# Terminal_Board_Schematic.net
KiCad netlist of a schematic drawn in Altium Designer
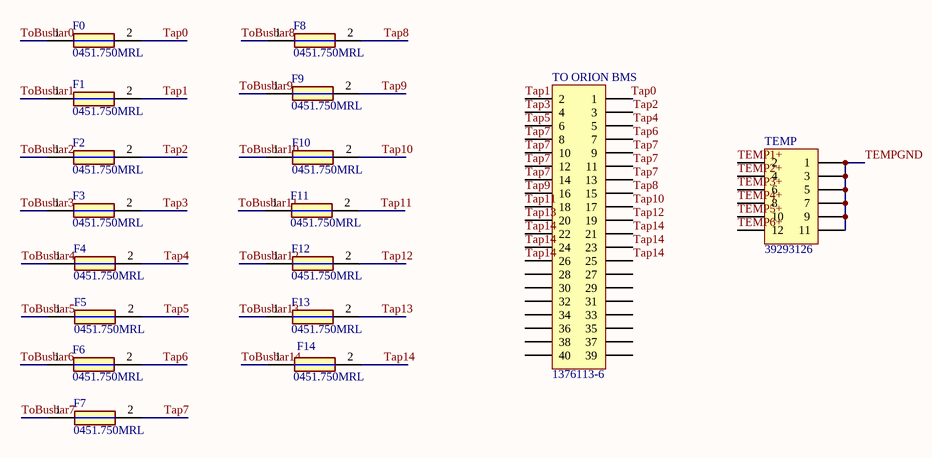
[diagram p0: Terminal Board Schematic.SchDoc]

(export (version "E")
  (design (tool "Eeschema 10.0.6"))
  (components
    (comp (ref "F0")
      (value "0451.750MRL")
      (footprint "SamacSys:FUSC6127X269N")
      (description "Fuse Chip Very Fast Acting 0.75A 125V SMD Solder Pad 2410 Ceramic T/R")
      (fields (field (name "MANUFACTURER") "Littelfuse"))
      (libsource (lib "*") (part "0451.750MRL"))
    )
    (comp (ref "F1")
      (value "0451.750MRL")
      (footprint "SamacSys:FUSC6127X269N")
      (description "Fuse Chip Very Fast Acting 0.75A 125V SMD Solder Pad 2410 Ceramic T/R")
      (fields (field (name "MANUFACTURER") "Littelfuse"))
      (libsource (lib "*") (part "0451.750MRL"))
    )
    (comp (ref "F2")
      (value "0451.750MRL")
      (footprint "SamacSys:FUSC6127X269N")
      (description "Fuse Chip Very Fast Acting 0.75A 125V SMD Solder Pad 2410 Ceramic T/R")
      (fields (field (name "MANUFACTURER") "Littelfuse"))
      (libsource (lib "*") (part "0451.750MRL"))
    )
    (comp (ref "F3")
      (value "0451.750MRL")
      (footprint "SamacSys:FUSC6127X269N")
      (description "Fuse Chip Very Fast Acting 0.75A 125V SMD Solder Pad 2410 Ceramic T/R")
      (fields (field (name "MANUFACTURER") "Littelfuse"))
      (libsource (lib "*") (part "0451.750MRL"))
    )
    (comp (ref "F4")
      (value "0451.750MRL")
      (footprint "SamacSys:FUSC6127X269N")
      (description "Fuse Chip Very Fast Acting 0.75A 125V SMD Solder Pad 2410 Ceramic T/R")
      (fields (field (name "MANUFACTURER") "Littelfuse"))
      (libsource (lib "*") (part "0451.750MRL"))
    )
    (comp (ref "F5")
      (value "0451.750MRL")
      (footprint "SamacSys:FUSC6127X269N")
      (description "Fuse Chip Very Fast Acting 0.75A 125V SMD Solder Pad 2410 Ceramic T/R")
      (fields (field (name "MANUFACTURER") "Littelfuse"))
      (libsource (lib "*") (part "0451.750MRL"))
    )
    (comp (ref "F6")
      (value "0451.750MRL")
      (footprint "SamacSys:FUSC6127X269N")
      (description "Fuse Chip Very Fast Acting 0.75A 125V SMD Solder Pad 2410 Ceramic T/R")
      (fields (field (name "MANUFACTURER") "Littelfuse"))
      (libsource (lib "*") (part "0451.750MRL"))
    )
    (comp (ref "F7")
      (value "0451.750MRL")
      (footprint "SamacSys:FUSC6127X269N")
      (description "Fuse Chip Very Fast Acting 0.75A 125V SMD Solder Pad 2410 Ceramic T/R")
      (fields (field (name "MANUFACTURER") "Littelfuse"))
      (libsource (lib "*") (part "0451.750MRL"))
    )
    (comp (ref "F8")
      (value "0451.750MRL")
      (footprint "SamacSys:FUSC6127X269N")
      (description "Fuse Chip Very Fast Acting 0.75A 125V SMD Solder Pad 2410 Ceramic T/R")
      (fields (field (name "MANUFACTURER") "Littelfuse"))
      (libsource (lib "*") (part "0451.750MRL"))
    )
    (comp (ref "F9")
      (value "0451.750MRL")
      (footprint "SamacSys:FUSC6127X269N")
      (description "Fuse Chip Very Fast Acting 0.75A 125V SMD Solder Pad 2410 Ceramic T/R")
      (fields (field (name "MANUFACTURER") "Littelfuse"))
      (libsource (lib "*") (part "0451.750MRL"))
    )
    (comp (ref "F10")
      (value "0451.750MRL")
      (footprint "SamacSys:FUSC6127X269N")
      (description "Fuse Chip Very Fast Acting 0.75A 125V SMD Solder Pad 2410 Ceramic T/R")
      (fields (field (name "MANUFACTURER") "Littelfuse"))
      (libsource (lib "*") (part "0451.750MRL"))
    )
    (comp (ref "F11")
      (value "0451.750MRL")
      (footprint "SamacSys:FUSC6127X269N")
      (description "Fuse Chip Very Fast Acting 0.75A 125V SMD Solder Pad 2410 Ceramic T/R")
      (fields (field (name "MANUFACTURER") "Littelfuse"))
      (libsource (lib "*") (part "0451.750MRL"))
    )
    (comp (ref "F12")
      (value "0451.750MRL")
      (footprint "SamacSys:FUSC6127X269N")
      (description "Fuse Chip Very Fast Acting 0.75A 125V SMD Solder Pad 2410 Ceramic T/R")
      (fields (field (name "MANUFACTURER") "Littelfuse"))
      (libsource (lib "*") (part "0451.750MRL"))
    )
    (comp (ref "F13")
      (value "0451.750MRL")
      (footprint "SamacSys:FUSC6127X269N")
      (description "Fuse Chip Very Fast Acting 0.75A 125V SMD Solder Pad 2410 Ceramic T/R")
      (fields (field (name "MANUFACTURER") "Littelfuse"))
      (libsource (lib "*") (part "0451.750MRL"))
    )
    (comp (ref "F14")
      (value "0451.750MRL")
      (footprint "SamacSys:FUSC6127X269N")
      (description "Fuse Chip Very Fast Acting 0.75A 125V SMD Solder Pad 2410 Ceramic T/R")
      (fields (field (name "MANUFACTURER") "Littelfuse"))
      (libsource (lib "*") (part "0451.750MRL"))
    )
    (comp (ref "TEMP")
      (value "39293126")
      (footprint "39293126")
      (fields
        (field (name "DIGIKEY PART NUMBER") "WM3848-ND")
        (field (name "MANUFACTURER") "Molex")
        (field (name "MANUFACTURER PART NUMBER") "39-29-3126")
        (field (name "CONTACT") "Tin")
      )
      (libsource (lib "ts_20-standard-connectors") (part "12"))
    )
    (comp (ref "TO ORION BMS")
      (value "1376113-6")
      (footprint "1376113-6")
      (description "ORION BMS 40 Pin Header")
      (fields (field (name "DIGIKEY PART NUMBER") "1376113-6-ND") (field (name "CONTACT") "Gold"))
      (libsource (lib "ts_20-standard-connectors") (part "1376113-6"))
    )
  )
  (nets
    (net (code "1") (name "/TEMP1+") (class "Default")
      (node (ref "TEMP") (pin "2") (pinfunction "2_2") (pintype "passive"))
    )
    (net (code "2") (name "/TEMP2+") (class "Default")
      (node (ref "TEMP") (pin "4") (pinfunction "4_4") (pintype "passive"))
    )
    (net (code "3") (name "/TEMP3+") (class "Default")
      (node (ref "TEMP") (pin "6") (pinfunction "6_6") (pintype "passive"))
    )
    (net (code "4") (name "/TEMP4+") (class "Default")
      (node (ref "TEMP") (pin "8") (pinfunction "8_8") (pintype "passive"))
    )
    (net (code "5") (name "/TEMP5+") (class "Default")
      (node (ref "TEMP") (pin "10") (pinfunction "10_10") (pintype "passive"))
    )
    (net (code "6") (name "/TEMP6+") (class "Default")
      (node (ref "TEMP") (pin "12") (pinfunction "12_12") (pintype "passive"))
    )
    (net (code "7") (name "/TEMPGND") (class "Default")
      (node (ref "TEMP") (pin "1") (pinfunction "1_1") (pintype "passive"))
      (node (ref "TEMP") (pin "11") (pinfunction "11_11") (pintype "passive"))
      (node (ref "TEMP") (pin "3") (pinfunction "3_3") (pintype "passive"))
      (node (ref "TEMP") (pin "5") (pinfunction "5_5") (pintype "passive"))
      (node (ref "TEMP") (pin "7") (pinfunction "7_7") (pintype "passive"))
      (node (ref "TEMP") (pin "9") (pinfunction "9_9") (pintype "passive"))
    )
    (net (code "8") (name "/Tap0") (class "Default")
      (node (ref "F0") (pin "2") (pinfunction "2_2") (pintype "passive"))
      (node (ref "TO ORION BMS") (pin "1") (pinfunction "1_1") (pintype "passive"))
    )
    (net (code "9") (name "/Tap1") (class "Default")
      (node (ref "F1") (pin "2") (pinfunction "2_2") (pintype "passive"))
      (node (ref "TO ORION BMS") (pin "2") (pinfunction "2_2") (pintype "passive"))
    )
    (net (code "10") (name "/Tap2") (class "Default")
      (node (ref "F2") (pin "2") (pinfunction "2_2") (pintype "passive"))
      (node (ref "TO ORION BMS") (pin "3") (pinfunction "3_3") (pintype "passive"))
    )
    (net (code "11") (name "/Tap3") (class "Default")
      (node (ref "F3") (pin "2") (pinfunction "2_2") (pintype "passive"))
      (node (ref "TO ORION BMS") (pin "4") (pinfunction "4_4") (pintype "passive"))
    )
    (net (code "12") (name "/Tap4") (class "Default")
      (node (ref "F4") (pin "2") (pinfunction "2_2") (pintype "passive"))
      (node (ref "TO ORION BMS") (pin "5") (pinfunction "5_5") (pintype "passive"))
    )
    (net (code "13") (name "/Tap5") (class "Default")
      (node (ref "F5") (pin "2") (pinfunction "2_2") (pintype "passive"))
      (node (ref "TO ORION BMS") (pin "6") (pinfunction "6_6") (pintype "passive"))
    )
    (net (code "14") (name "/Tap6") (class "Default")
      (node (ref "F6") (pin "2") (pinfunction "2_2") (pintype "passive"))
      (node (ref "TO ORION BMS") (pin "7") (pinfunction "7_7") (pintype "passive"))
    )
    (net (code "15") (name "/Tap7") (class "Default")
      (node (ref "F7") (pin "2") (pinfunction "2_2") (pintype "passive"))
      (node (ref "TO ORION BMS") (pin "10") (pinfunction "10_10") (pintype "passive"))
      (node (ref "TO ORION BMS") (pin "11") (pinfunction "11_11") (pintype "passive"))
      (node (ref "TO ORION BMS") (pin "12") (pinfunction "12_12") (pintype "passive"))
      (node (ref "TO ORION BMS") (pin "13") (pinfunction "13_13") (pintype "passive"))
      (node (ref "TO ORION BMS") (pin "14") (pinfunction "14_14") (pintype "passive"))
      (node (ref "TO ORION BMS") (pin "8") (pinfunction "8_8") (pintype "passive"))
      (node (ref "TO ORION BMS") (pin "9") (pinfunction "9_9") (pintype "passive"))
    )
    (net (code "16") (name "/Tap8") (class "Default")
      (node (ref "F8") (pin "2") (pinfunction "2_2") (pintype "passive"))
      (node (ref "TO ORION BMS") (pin "15") (pinfunction "15_15") (pintype "passive"))
    )
    (net (code "17") (name "/Tap9") (class "Default")
      (node (ref "F9") (pin "2") (pinfunction "2_2") (pintype "passive"))
      (node (ref "TO ORION BMS") (pin "16") (pinfunction "16_16") (pintype "passive"))
    )
    (net (code "18") (name "/Tap10") (class "Default")
      (node (ref "F10") (pin "2") (pinfunction "2_2") (pintype "passive"))
      (node (ref "TO ORION BMS") (pin "17") (pinfunction "17_17") (pintype "passive"))
    )
    (net (code "19") (name "/Tap11") (class "Default")
      (node (ref "F11") (pin "2") (pinfunction "2_2") (pintype "passive"))
      (node (ref "TO ORION BMS") (pin "18") (pinfunction "18_18") (pintype "passive"))
    )
    (net (code "20") (name "/Tap12") (class "Default")
      (node (ref "F12") (pin "2") (pinfunction "2_2") (pintype "passive"))
      (node (ref "TO ORION BMS") (pin "19") (pinfunction "19_19") (pintype "passive"))
    )
    (net (code "21") (name "/Tap13") (class "Default")
      (node (ref "F13") (pin "2") (pinfunction "2_2") (pintype "passive"))
      (node (ref "TO ORION BMS") (pin "20") (pinfunction "20_20") (pintype "passive"))
    )
    (net (code "22") (name "/Tap14") (class "Default")
      (node (ref "F14") (pin "2") (pinfunction "2_2") (pintype "passive"))
      (node (ref "TO ORION BMS") (pin "21") (pinfunction "21_21") (pintype "passive"))
      (node (ref "TO ORION BMS") (pin "22") (pinfunction "22_22") (pintype "passive"))
      (node (ref "TO ORION BMS") (pin "23") (pinfunction "23_23") (pintype "passive"))
      (node (ref "TO ORION BMS") (pin "24") (pinfunction "24_24") (pintype "passive"))
      (node (ref "TO ORION BMS") (pin "25") (pinfunction "25_25") (pintype "passive"))
      (node (ref "TO ORION BMS") (pin "26") (pinfunction "26_26") (pintype "passive"))
    )
    (net (code "23") (name "/ToBusbar0") (class "Default")
      (node (ref "F0") (pin "1") (pinfunction "1_1") (pintype "passive"))
    )
    (net (code "24") (name "/ToBusbar1") (class "Default")
      (node (ref "F1") (pin "1") (pinfunction "1_1") (pintype "passive"))
    )
    (net (code "25") (name "/ToBusbar2") (class "Default")
      (node (ref "F2") (pin "1") (pinfunction "1_1") (pintype "passive"))
    )
    (net (code "26") (name "/ToBusbar3") (class "Default")
      (node (ref "F3") (pin "1") (pinfunction "1_1") (pintype "passive"))
    )
    (net (code "27") (name "/ToBusbar4") (class "Default")
      (node (ref "F4") (pin "1") (pinfunction "1_1") (pintype "passive"))
    )
    (net (code "28") (name "/ToBusbar5") (class "Default")
      (node (ref "F5") (pin "1") (pinfunction "1_1") (pintype "passive"))
    )
    (net (code "29") (name "/ToBusbar6") (class "Default")
      (node (ref "F6") (pin "1") (pinfunction "1_1") (pintype "passive"))
    )
    (net (code "30") (name "/ToBusbar7") (class "Default")
      (node (ref "F7") (pin "1") (pinfunction "1_1") (pintype "passive"))
    )
    (net (code "31") (name "/ToBusbar8") (class "Default")
      (node (ref "F8") (pin "1") (pinfunction "1_1") (pintype "passive"))
    )
    (net (code "32") (name "/ToBusbar9") (class "Default")
      (node (ref "F9") (pin "1") (pinfunction "1_1") (pintype "passive"))
    )
    (net (code "33") (name "/ToBusbar10") (class "Default")
      (node (ref "F10") (pin "1") (pinfunction "1_1") (pintype "passive"))
    )
    (net (code "34") (name "/ToBusbar11") (class "Default")
      (node (ref "F11") (pin "1") (pinfunction "1_1") (pintype "passive"))
    )
    (net (code "35") (name "/ToBusbar12") (class "Default")
      (node (ref "F12") (pin "1") (pinfunction "1_1") (pintype "passive"))
    )
    (net (code "36") (name "/ToBusbar13") (class "Default")
      (node (ref "F13") (pin "1") (pinfunction "1_1") (pintype "passive"))
    )
    (net (code "37") (name "/ToBusbar14") (class "Default")
      (node (ref "F14") (pin "1") (pinfunction "1_1") (pintype "passive"))
    )
    (net (code "38") (name "unconnected-(TO ORION BMS-Pad27)") (class "Default")
      (node (ref "TO ORION BMS") (pin "27") (pinfunction "27_27") (pintype "passive"))
    )
    (net (code "39") (name "unconnected-(TO ORION BMS-Pad28)") (class "Default")
      (node (ref "TO ORION BMS") (pin "28") (pinfunction "28_28") (pintype "passive"))
    )
    (net (code "40") (name "unconnected-(TO ORION BMS-Pad29)") (class "Default")
      (node (ref "TO ORION BMS") (pin "29") (pinfunction "29_29") (pintype "passive"))
    )
    (net (code "41") (name "unconnected-(TO ORION BMS-Pad30)") (class "Default")
      (node (ref "TO ORION BMS") (pin "30") (pinfunction "30_30") (pintype "passive"))
    )
    (net (code "42") (name "unconnected-(TO ORION BMS-Pad31)") (class "Default")
      (node (ref "TO ORION BMS") (pin "31") (pinfunction "31_31") (pintype "passive"))
    )
    (net (code "43") (name "unconnected-(TO ORION BMS-Pad32)") (class "Default")
      (node (ref "TO ORION BMS") (pin "32") (pinfunction "32_32") (pintype "passive"))
    )
    (net (code "44") (name "unconnected-(TO ORION BMS-Pad33)") (class "Default")
      (node (ref "TO ORION BMS") (pin "33") (pinfunction "33_33") (pintype "passive"))
    )
    (net (code "45") (name "unconnected-(TO ORION BMS-Pad34)") (class "Default")
      (node (ref "TO ORION BMS") (pin "34") (pinfunction "34_34") (pintype "passive"))
    )
    (net (code "46") (name "unconnected-(TO ORION BMS-Pad35)") (class "Default")
      (node (ref "TO ORION BMS") (pin "35") (pinfunction "35_35") (pintype "passive"))
    )
    (net (code "47") (name "unconnected-(TO ORION BMS-Pad36)") (class "Default")
      (node (ref "TO ORION BMS") (pin "36") (pinfunction "36_36") (pintype "passive"))
    )
    (net (code "48") (name "unconnected-(TO ORION BMS-Pad37)") (class "Default")
      (node (ref "TO ORION BMS") (pin "37") (pinfunction "37_37") (pintype "passive"))
    )
    (net (code "49") (name "unconnected-(TO ORION BMS-Pad38)") (class "Default")
      (node (ref "TO ORION BMS") (pin "38") (pinfunction "38_38") (pintype "passive"))
    )
    (net (code "50") (name "unconnected-(TO ORION BMS-Pad39)") (class "Default")
      (node (ref "TO ORION BMS") (pin "39") (pinfunction "39_39") (pintype "passive"))
    )
    (net (code "51") (name "unconnected-(TO ORION BMS-Pad40)") (class "Default")
      (node (ref "TO ORION BMS") (pin "40") (pinfunction "40_40") (pintype "passive"))
    )
  )
)
